# Charger_Main_Power.net
KiCad netlist of a schematic drawn in Altium Designer
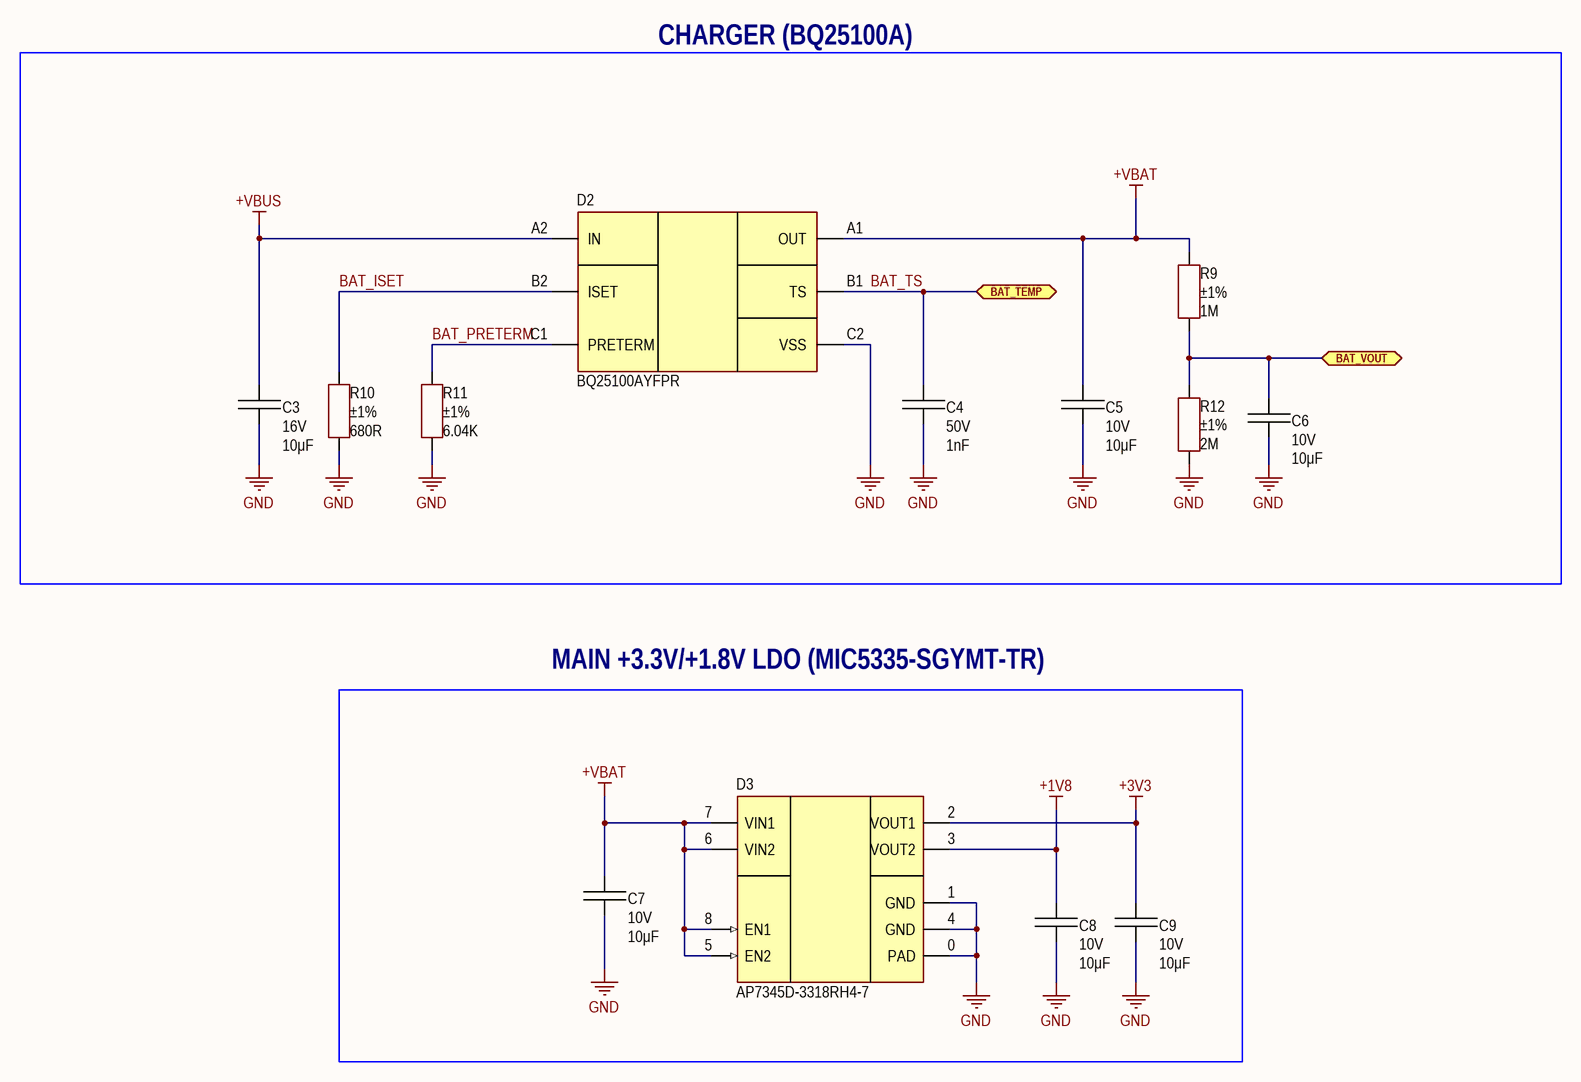
[diagram p0: Charger+Main_Power.SchDoc]

(export (version "E")
  (design (tool "Eeschema 10.0.6"))
  (components
    (comp (ref "C3")
      (value "10μF")
      (footprint "CAP: 0805")
      (description "10 µF ±20% 16V Ceramic Capacitor X7R 0805 (2012 Metric)")
      (fields
        (field (name "MANUFACTURER") "Yageo")
        (field (name "PARTNUMBER") "CC0805MKX7R7BB106")
        (field (name "VOLTAGE") "16V")
      )
      (libsource (lib "capacitor") (part "Ceramic_0805"))
    )
    (comp (ref "C4")
      (value "1nF")
      (footprint "CAP: 0805")
      (description "1000 pF ±5% 50V Ceramic Capacitor C0G, NP0 0805 (2012 Metric)")
      (fields
        (field (name "MANUFACTURER") "Yageo")
        (field (name "PARTNUMBER") "CC0805JRNPO9BN102")
        (field (name "VOLTAGE") "50V")
      )
      (libsource (lib "capacitor") (part "Ceramic_0805"))
    )
    (comp (ref "C5")
      (value "10μF")
      (footprint "CAP: 0805")
      (description "10 µF ±10% 10V Ceramic Capacitor X7R 0805 (2012 Metric)")
      (fields
        (field (name "MANUFACTURER") "Yageo")
        (field (name "PARTNUMBER") "CC0805KFX7R6BB106")
        (field (name "VOLTAGE") "10V")
      )
      (libsource (lib "capacitor") (part "Ceramic_0805"))
    )
    (comp (ref "C6")
      (value "10μF")
      (footprint "CAP: 0805")
      (description "10 µF ±10% 10V Ceramic Capacitor X7R 0805 (2012 Metric)")
      (fields
        (field (name "MANUFACTURER") "Yageo")
        (field (name "PARTNUMBER") "CC0805KFX7R6BB106")
        (field (name "VOLTAGE") "10V")
      )
      (libsource (lib "capacitor") (part "Ceramic_0805"))
    )
    (comp (ref "C7")
      (value "10μF")
      (footprint "CAP: 0805")
      (description "10 µF ±10% 10V Ceramic Capacitor X7R 0805 (2012 Metric)")
      (fields
        (field (name "MANUFACTURER") "Yageo")
        (field (name "PARTNUMBER") "CC0805KFX7R6BB106")
        (field (name "VOLTAGE") "10V")
      )
      (libsource (lib "capacitor") (part "Ceramic_0805"))
    )
    (comp (ref "C8")
      (value "10μF")
      (footprint "CAP: 0805")
      (description "10 µF ±10% 10V Ceramic Capacitor X7R 0805 (2012 Metric)")
      (fields
        (field (name "MANUFACTURER") "Yageo")
        (field (name "PARTNUMBER") "CC0805KFX7R6BB106")
        (field (name "VOLTAGE") "10V")
      )
      (libsource (lib "capacitor") (part "Ceramic_0805"))
    )
    (comp (ref "C9")
      (value "10μF")
      (footprint "CAP: 0805")
      (description "10 µF ±10% 10V Ceramic Capacitor X7R 0805 (2012 Metric)")
      (fields
        (field (name "MANUFACTURER") "Yageo")
        (field (name "PARTNUMBER") "CC0805KFX7R6BB106")
        (field (name "VOLTAGE") "10V")
      )
      (libsource (lib "capacitor") (part "Ceramic_0805"))
    )
    (comp (ref "D2")
      (value "~")
      (footprint "IC: BQ25100")
      (description "PMIC")
      (fields
        (field (name "MANUFACTURER") "Texas Instruments")
        (field (name "VALUEMANUFACTURERPARTNUMBER") "PMIC, Li-Ion/Li-Po, 4.45...6.45V, -40...+85°C, 10-WSON")
        (field (name "PARTNUMBER") "BQ25100AYFPR")
      )
      (libsource (lib "MyLib") (part "BQ25100AYFPR"))
    )
    (comp (ref "D3")
      (value "~")
      (footprint "IC: 8-XFDFN")
      (description "Linear voltage regulator")
      (fields
        (field (name "MANUFACTURER") "Diodes Incorporated")
        (field (name "VALUEMANUFACTURERPARTNUMBER") "Linear voltage regulator, input 3.6...5.25V, 0.39V, 3.3V/1.8V, 0.3A, -40...+125°C, 8-XFDFN")
        (field (name "PARTNUMBER") "AP7345D-3318RH4-7")
      )
      (libsource (lib "MyLib") (part "AP7345D-3318RH4-7"))
    )
    (comp (ref "R9")
      (value "1M")
      (footprint "RES: 0805")
      (description "1 MOhms ±1% 0.125W, 1/8W Chip Resistor 0805 (2012 Metric) Moisture Resistant Thick Film")
      (fields
        (field (name "MANUFACTURER") "Yageo")
        (field (name "PARTNUMBER") "RC0805FR-071ML")
        (field (name "TOLERANCE") "±1%")
      )
      (libsource (lib "resistor") (part "Resistor_0805"))
    )
    (comp (ref "R10")
      (value "680R")
      (footprint "RES: 0805")
      (description "680 Ohms ±1% 0.125W, 1/8W Chip Resistor 0805 (2012 Metric) Moisture Resistant Thick Film")
      (fields
        (field (name "MANUFACTURER") "Yageo")
        (field (name "PARTNUMBER") "RC0805FR-07680RL")
        (field (name "TOLERANCE") "±1%")
      )
      (libsource (lib "resistor") (part "Resistor_0805"))
    )
    (comp (ref "R11")
      (value "6.04K")
      (footprint "RES: 0805")
      (description "6.04 kOhms ±1% 0.125W, 1/8W Chip Resistor 0805 (2012 Metric) Moisture Resistant Thick Film")
      (fields
        (field (name "MANUFACTURER") "Yageo")
        (field (name "PARTNUMBER") "RC0805FR-076K04L")
        (field (name "TOLERANCE") "±1%")
      )
      (libsource (lib "resistor") (part "Resistor_0805"))
    )
    (comp (ref "R12")
      (value "2M")
      (footprint "RES: 0805")
      (description "2 MOhms ±1% 0.125W, 1/8W Chip Resistor 0805 (2012 Metric) Moisture Resistant Thick Film")
      (fields
        (field (name "MANUFACTURER") "Yageo")
        (field (name "PARTNUMBER") "RC0805FR-072ML")
        (field (name "TOLERANCE") "±1%")
      )
      (libsource (lib "resistor") (part "Resistor_0805"))
    )
  )
  (nets
    (net (code "1") (name "+1V8") (class "Default")
      (node (ref "C8") (pin "2") (pinfunction "2_2") (pintype "passive"))
      (node (ref "D3") (pin "3") (pinfunction "VOUT2_3") (pintype "power_in"))
    )
    (net (code "2") (name "+3V3") (class "Default")
      (node (ref "C9") (pin "2") (pinfunction "2_2") (pintype "passive"))
      (node (ref "D3") (pin "2") (pinfunction "VOUT1_2") (pintype "power_in"))
    )
    (net (code "3") (name "+VBAT") (class "Default")
      (node (ref "C5") (pin "2") (pinfunction "2_2") (pintype "passive"))
      (node (ref "C7") (pin "2") (pinfunction "2_2") (pintype "passive"))
      (node (ref "D2") (pin "A1") (pinfunction "OUT_A1") (pintype "passive"))
      (node (ref "D3") (pin "5") (pinfunction "EN2_5") (pintype "input"))
      (node (ref "D3") (pin "6") (pinfunction "VIN2_6") (pintype "power_in"))
      (node (ref "D3") (pin "7") (pinfunction "VIN1_7") (pintype "power_in"))
      (node (ref "D3") (pin "8") (pinfunction "EN1_8") (pintype "input"))
      (node (ref "R9") (pin "1") (pinfunction "1_1") (pintype "passive"))
    )
    (net (code "4") (name "+VBUS") (class "Default")
      (node (ref "C3") (pin "2") (pinfunction "2_2") (pintype "passive"))
      (node (ref "D2") (pin "A2") (pinfunction "IN_A2") (pintype "passive"))
    )
    (net (code "5") (name "/BAT_ISET") (class "Default")
      (node (ref "D2") (pin "B2") (pinfunction "ISET_B2") (pintype "passive"))
      (node (ref "R10") (pin "1") (pinfunction "1_1") (pintype "passive"))
    )
    (net (code "6") (name "/BAT_PRETERM") (class "Default")
      (node (ref "D2") (pin "C1") (pinfunction "PRETERM_C1") (pintype "passive"))
      (node (ref "R11") (pin "1") (pinfunction "1_1") (pintype "passive"))
    )
    (net (code "7") (name "/BAT_TS") (class "Default")
      (node (ref "C4") (pin "2") (pinfunction "2_2") (pintype "passive"))
      (node (ref "D2") (pin "B1") (pinfunction "TS_B1") (pintype "passive"))
    )
    (net (code "8") (name "/BAT_VOUT") (class "Default")
      (node (ref "C6") (pin "2") (pinfunction "2_2") (pintype "passive"))
      (node (ref "R12") (pin "1") (pinfunction "1_1") (pintype "passive"))
      (node (ref "R9") (pin "2") (pinfunction "2_2") (pintype "passive"))
    )
    (net (code "9") (name "GND") (class "Default")
      (node (ref "C3") (pin "1") (pinfunction "1_1") (pintype "passive"))
      (node (ref "C4") (pin "1") (pinfunction "1_1") (pintype "passive"))
      (node (ref "C5") (pin "1") (pinfunction "1_1") (pintype "passive"))
      (node (ref "C6") (pin "1") (pinfunction "1_1") (pintype "passive"))
      (node (ref "C7") (pin "1") (pinfunction "1_1") (pintype "passive"))
      (node (ref "C8") (pin "1") (pinfunction "1_1") (pintype "passive"))
      (node (ref "C9") (pin "1") (pinfunction "1_1") (pintype "passive"))
      (node (ref "D2") (pin "C2") (pinfunction "VSS_C2") (pintype "passive"))
      (node (ref "D3") (pin "0") (pinfunction "PAD_0") (pintype "power_in"))
      (node (ref "D3") (pin "1") (pinfunction "GND_1") (pintype "power_in"))
      (node (ref "D3") (pin "4") (pinfunction "GND_4") (pintype "power_in"))
      (node (ref "R10") (pin "2") (pinfunction "2_2") (pintype "passive"))
      (node (ref "R11") (pin "2") (pinfunction "2_2") (pintype "passive"))
      (node (ref "R12") (pin "2") (pinfunction "2_2") (pintype "passive"))
    )
  )
)
